# retr3d-testbench.net
KiCad netlist of a schematic drawn in EAGLE
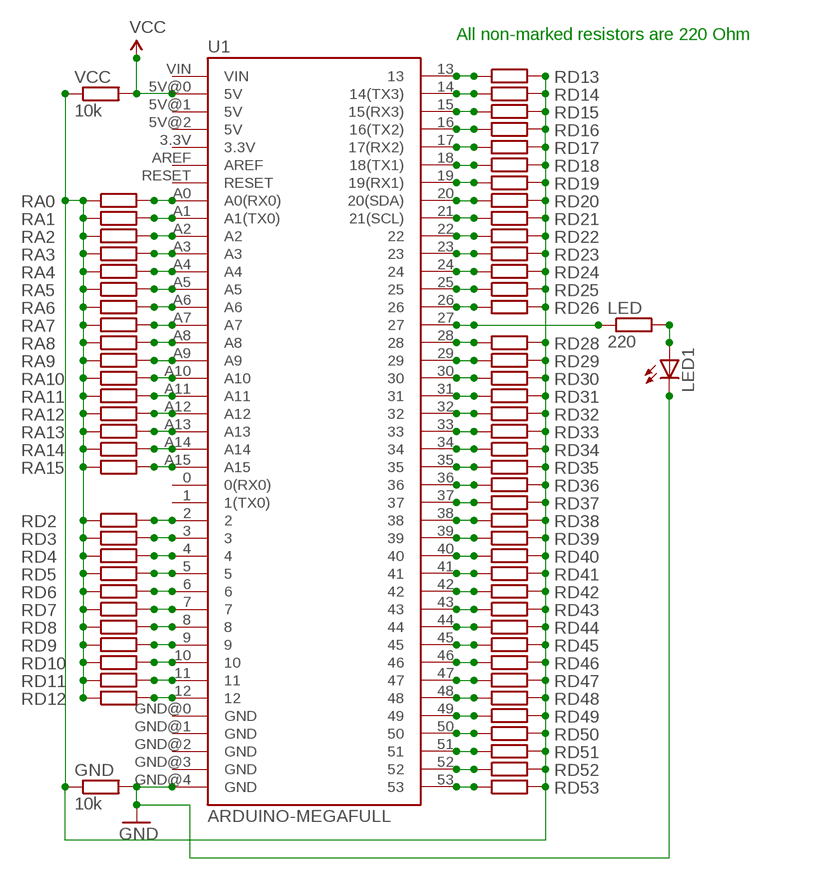
[diagram p0: schematic, sheet 1]

(export (version "E")
  (design (tool "Eeschema 10.0.6"))
  (components
    (comp (ref "GND")
      (value "10k")
      (footprint "eagle-import:0207_10")
      (libsource (lib "eagle-import") (part "R0207/10"))
    )
    (comp (ref "LED")
      (value "220")
      (footprint "eagle-import:0207_10")
      (libsource (lib "eagle-import") (part "R0207/10"))
    )
    (comp (ref "LED1")
      (value "LED5MM")
      (footprint "eagle-import:LED5MM")
      (libsource (lib "eagle-import") (part "LED5MM"))
    )
    (comp (ref "RA0")
      (value "220")
      (footprint "eagle-import:0207_10")
      (libsource (lib "eagle-import") (part "R0207/10"))
    )
    (comp (ref "RA1")
      (value "220")
      (footprint "eagle-import:0207_10")
      (libsource (lib "eagle-import") (part "R0207/10"))
    )
    (comp (ref "RA2")
      (value "220")
      (footprint "eagle-import:0207_10")
      (libsource (lib "eagle-import") (part "R0207/10"))
    )
    (comp (ref "RA3")
      (value "220")
      (footprint "eagle-import:0207_10")
      (libsource (lib "eagle-import") (part "R0207/10"))
    )
    (comp (ref "RA4")
      (value "220")
      (footprint "eagle-import:0207_10")
      (libsource (lib "eagle-import") (part "R0207/10"))
    )
    (comp (ref "RA5")
      (value "220")
      (footprint "eagle-import:0207_10")
      (libsource (lib "eagle-import") (part "R0207/10"))
    )
    (comp (ref "RA6")
      (value "220")
      (footprint "eagle-import:0207_10")
      (libsource (lib "eagle-import") (part "R0207/10"))
    )
    (comp (ref "RA7")
      (value "220")
      (footprint "eagle-import:0207_10")
      (libsource (lib "eagle-import") (part "R0207/10"))
    )
    (comp (ref "RA8")
      (value "220")
      (footprint "eagle-import:0207_10")
      (libsource (lib "eagle-import") (part "R0207/10"))
    )
    (comp (ref "RA9")
      (value "220")
      (footprint "eagle-import:0207_10")
      (libsource (lib "eagle-import") (part "R0207/10"))
    )
    (comp (ref "RA10")
      (value "220")
      (footprint "eagle-import:0207_10")
      (libsource (lib "eagle-import") (part "R0207/10"))
    )
    (comp (ref "RA11")
      (value "220")
      (footprint "eagle-import:0207_10")
      (libsource (lib "eagle-import") (part "R0207/10"))
    )
    (comp (ref "RA12")
      (value "220")
      (footprint "eagle-import:0207_10")
      (libsource (lib "eagle-import") (part "R0207/10"))
    )
    (comp (ref "RA13")
      (value "220")
      (footprint "eagle-import:0207_10")
      (libsource (lib "eagle-import") (part "R0207/10"))
    )
    (comp (ref "RA14")
      (value "220")
      (footprint "eagle-import:0207_10")
      (libsource (lib "eagle-import") (part "R0207/10"))
    )
    (comp (ref "RA15")
      (value "220")
      (footprint "eagle-import:0207_10")
      (libsource (lib "eagle-import") (part "R0207/10"))
    )
    (comp (ref "RD2")
      (value "220")
      (footprint "eagle-import:0207_10")
      (libsource (lib "eagle-import") (part "R0207/10"))
    )
    (comp (ref "RD3")
      (value "220")
      (footprint "eagle-import:0207_10")
      (libsource (lib "eagle-import") (part "R0207/10"))
    )
    (comp (ref "RD4")
      (value "220")
      (footprint "eagle-import:0207_10")
      (libsource (lib "eagle-import") (part "R0207/10"))
    )
    (comp (ref "RD5")
      (value "220")
      (footprint "eagle-import:0207_10")
      (libsource (lib "eagle-import") (part "R0207/10"))
    )
    (comp (ref "RD6")
      (value "220")
      (footprint "eagle-import:0207_10")
      (libsource (lib "eagle-import") (part "R0207/10"))
    )
    (comp (ref "RD7")
      (value "220")
      (footprint "eagle-import:0207_10")
      (libsource (lib "eagle-import") (part "R0207/10"))
    )
    (comp (ref "RD8")
      (value "220")
      (footprint "eagle-import:0207_10")
      (libsource (lib "eagle-import") (part "R0207/10"))
    )
    (comp (ref "RD9")
      (value "220")
      (footprint "eagle-import:0207_10")
      (libsource (lib "eagle-import") (part "R0207/10"))
    )
    (comp (ref "RD10")
      (value "220")
      (footprint "eagle-import:0207_10")
      (libsource (lib "eagle-import") (part "R0207/10"))
    )
    (comp (ref "RD11")
      (value "220")
      (footprint "eagle-import:0207_10")
      (libsource (lib "eagle-import") (part "R0207/10"))
    )
    (comp (ref "RD12")
      (value "220")
      (footprint "eagle-import:0207_10")
      (libsource (lib "eagle-import") (part "R0207/10"))
    )
    (comp (ref "RD13")
      (value "220")
      (footprint "eagle-import:0207_10")
      (libsource (lib "eagle-import") (part "R0207/10"))
    )
    (comp (ref "RD14")
      (value "220")
      (footprint "eagle-import:0207_10")
      (libsource (lib "eagle-import") (part "R0207/10"))
    )
    (comp (ref "RD15")
      (value "220")
      (footprint "eagle-import:0207_10")
      (libsource (lib "eagle-import") (part "R0207/10"))
    )
    (comp (ref "RD16")
      (value "220")
      (footprint "eagle-import:0207_10")
      (libsource (lib "eagle-import") (part "R0207/10"))
    )
    (comp (ref "RD17")
      (value "220")
      (footprint "eagle-import:0207_10")
      (libsource (lib "eagle-import") (part "R0207/10"))
    )
    (comp (ref "RD18")
      (value "220")
      (footprint "eagle-import:0207_10")
      (libsource (lib "eagle-import") (part "R0207/10"))
    )
    (comp (ref "RD19")
      (value "220")
      (footprint "eagle-import:0207_10")
      (libsource (lib "eagle-import") (part "R0207/10"))
    )
    (comp (ref "RD20")
      (value "220")
      (footprint "eagle-import:0207_10")
      (libsource (lib "eagle-import") (part "R0207/10"))
    )
    (comp (ref "RD21")
      (value "220")
      (footprint "eagle-import:0207_10")
      (libsource (lib "eagle-import") (part "R0207/10"))
    )
    (comp (ref "RD22")
      (value "220")
      (footprint "eagle-import:0207_10")
      (libsource (lib "eagle-import") (part "R0207/10"))
    )
    (comp (ref "RD23")
      (value "220")
      (footprint "eagle-import:0207_10")
      (libsource (lib "eagle-import") (part "R0207/10"))
    )
    (comp (ref "RD24")
      (value "220")
      (footprint "eagle-import:0207_10")
      (libsource (lib "eagle-import") (part "R0207/10"))
    )
    (comp (ref "RD25")
      (value "220")
      (footprint "eagle-import:0207_10")
      (libsource (lib "eagle-import") (part "R0207/10"))
    )
    (comp (ref "RD26")
      (value "220")
      (footprint "eagle-import:0207_10")
      (libsource (lib "eagle-import") (part "R0207/10"))
    )
    (comp (ref "RD28")
      (value "220")
      (footprint "eagle-import:0207_10")
      (libsource (lib "eagle-import") (part "R0207/10"))
    )
    (comp (ref "RD29")
      (value "220")
      (footprint "eagle-import:0207_10")
      (libsource (lib "eagle-import") (part "R0207/10"))
    )
    (comp (ref "RD30")
      (value "220")
      (footprint "eagle-import:0207_10")
      (libsource (lib "eagle-import") (part "R0207/10"))
    )
    (comp (ref "RD31")
      (value "220")
      (footprint "eagle-import:0207_10")
      (libsource (lib "eagle-import") (part "R0207/10"))
    )
    (comp (ref "RD32")
      (value "220")
      (footprint "eagle-import:0207_10")
      (libsource (lib "eagle-import") (part "R0207/10"))
    )
    (comp (ref "RD33")
      (value "220")
      (footprint "eagle-import:0207_10")
      (libsource (lib "eagle-import") (part "R0207/10"))
    )
    (comp (ref "RD34")
      (value "220")
      (footprint "eagle-import:0207_10")
      (libsource (lib "eagle-import") (part "R0207/10"))
    )
    (comp (ref "RD35")
      (value "220")
      (footprint "eagle-import:0207_10")
      (libsource (lib "eagle-import") (part "R0207/10"))
    )
    (comp (ref "RD36")
      (value "220")
      (footprint "eagle-import:0207_10")
      (libsource (lib "eagle-import") (part "R0207/10"))
    )
    (comp (ref "RD37")
      (value "220")
      (footprint "eagle-import:0207_10")
      (libsource (lib "eagle-import") (part "R0207/10"))
    )
    (comp (ref "RD38")
      (value "220")
      (footprint "eagle-import:0207_10")
      (libsource (lib "eagle-import") (part "R0207/10"))
    )
    (comp (ref "RD39")
      (value "220")
      (footprint "eagle-import:0207_10")
      (libsource (lib "eagle-import") (part "R0207/10"))
    )
    (comp (ref "RD40")
      (value "220")
      (footprint "eagle-import:0207_10")
      (libsource (lib "eagle-import") (part "R0207/10"))
    )
    (comp (ref "RD41")
      (value "220")
      (footprint "eagle-import:0207_10")
      (libsource (lib "eagle-import") (part "R0207/10"))
    )
    (comp (ref "RD42")
      (value "220")
      (footprint "eagle-import:0207_10")
      (libsource (lib "eagle-import") (part "R0207/10"))
    )
    (comp (ref "RD43")
      (value "220")
      (footprint "eagle-import:0207_10")
      (libsource (lib "eagle-import") (part "R0207/10"))
    )
    (comp (ref "RD44")
      (value "220")
      (footprint "eagle-import:0207_10")
      (libsource (lib "eagle-import") (part "R0207/10"))
    )
    (comp (ref "RD45")
      (value "220")
      (footprint "eagle-import:0207_10")
      (libsource (lib "eagle-import") (part "R0207/10"))
    )
    (comp (ref "RD46")
      (value "220")
      (footprint "eagle-import:0207_10")
      (libsource (lib "eagle-import") (part "R0207/10"))
    )
    (comp (ref "RD47")
      (value "220")
      (footprint "eagle-import:0207_10")
      (libsource (lib "eagle-import") (part "R0207/10"))
    )
    (comp (ref "RD48")
      (value "220")
      (footprint "eagle-import:0207_10")
      (libsource (lib "eagle-import") (part "R0207/10"))
    )
    (comp (ref "RD49")
      (value "220")
      (footprint "eagle-import:0207_10")
      (libsource (lib "eagle-import") (part "R0207/10"))
    )
    (comp (ref "RD50")
      (value "220")
      (footprint "eagle-import:0207_10")
      (libsource (lib "eagle-import") (part "R0207/10"))
    )
    (comp (ref "RD51")
      (value "220")
      (footprint "eagle-import:0207_10")
      (libsource (lib "eagle-import") (part "R0207/10"))
    )
    (comp (ref "RD52")
      (value "220")
      (footprint "eagle-import:0207_10")
      (libsource (lib "eagle-import") (part "R0207/10"))
    )
    (comp (ref "RD53")
      (value "220")
      (footprint "eagle-import:0207_10")
      (libsource (lib "eagle-import") (part "R0207/10"))
    )
    (comp (ref "U1")
      (value "ARDUINO-MEGAFULL")
      (footprint "eagle-import:ARDUINO_MEGA")
      (libsource (lib "eagle-import") (part "ARDUINO-MEGAFULL"))
    )
    (comp (ref "VCC")
      (value "10k")
      (footprint "eagle-import:0207_10")
      (libsource (lib "eagle-import") (part "R0207/10"))
    )
  )
  (nets
    (net (code "1") (name "GND") (class "Default")
      (node (ref "GND") (pin "2") (pinfunction "2_2") (pintype "passive"))
      (node (ref "LED1") (pin "K") (pinfunction "C_K") (pintype "passive"))
      (node (ref "U1") (pin "GND@4") (pinfunction "GND_GND@4") (pintype "bidirectional"))
    )
    (net (code "2") (name "Net-(GND-Pad1)") (class "Default")
      (node (ref "GND") (pin "1") (pinfunction "1_1") (pintype "passive"))
      (node (ref "RA0") (pin "1") (pinfunction "1_1") (pintype "passive"))
      (node (ref "RA1") (pin "1") (pinfunction "1_1") (pintype "passive"))
      (node (ref "RA10") (pin "1") (pinfunction "1_1") (pintype "passive"))
      (node (ref "RA11") (pin "1") (pinfunction "1_1") (pintype "passive"))
      (node (ref "RA12") (pin "1") (pinfunction "1_1") (pintype "passive"))
      (node (ref "RA13") (pin "1") (pinfunction "1_1") (pintype "passive"))
      (node (ref "RA14") (pin "1") (pinfunction "1_1") (pintype "passive"))
      (node (ref "RA15") (pin "1") (pinfunction "1_1") (pintype "passive"))
      (node (ref "RA2") (pin "1") (pinfunction "1_1") (pintype "passive"))
      (node (ref "RA3") (pin "1") (pinfunction "1_1") (pintype "passive"))
      (node (ref "RA4") (pin "1") (pinfunction "1_1") (pintype "passive"))
      (node (ref "RA5") (pin "1") (pinfunction "1_1") (pintype "passive"))
      (node (ref "RA6") (pin "1") (pinfunction "1_1") (pintype "passive"))
      (node (ref "RA7") (pin "1") (pinfunction "1_1") (pintype "passive"))
      (node (ref "RA8") (pin "1") (pinfunction "1_1") (pintype "passive"))
      (node (ref "RA9") (pin "1") (pinfunction "1_1") (pintype "passive"))
      (node (ref "RD10") (pin "1") (pinfunction "1_1") (pintype "passive"))
      (node (ref "RD11") (pin "1") (pinfunction "1_1") (pintype "passive"))
      (node (ref "RD12") (pin "1") (pinfunction "1_1") (pintype "passive"))
      (node (ref "RD13") (pin "2") (pinfunction "2_2") (pintype "passive"))
      (node (ref "RD14") (pin "2") (pinfunction "2_2") (pintype "passive"))
      (node (ref "RD15") (pin "2") (pinfunction "2_2") (pintype "passive"))
      (node (ref "RD16") (pin "2") (pinfunction "2_2") (pintype "passive"))
      (node (ref "RD17") (pin "2") (pinfunction "2_2") (pintype "passive"))
      (node (ref "RD18") (pin "2") (pinfunction "2_2") (pintype "passive"))
      (node (ref "RD19") (pin "2") (pinfunction "2_2") (pintype "passive"))
      (node (ref "RD2") (pin "1") (pinfunction "1_1") (pintype "passive"))
      (node (ref "RD20") (pin "2") (pinfunction "2_2") (pintype "passive"))
      (node (ref "RD21") (pin "2") (pinfunction "2_2") (pintype "passive"))
      (node (ref "RD22") (pin "2") (pinfunction "2_2") (pintype "passive"))
      (node (ref "RD23") (pin "2") (pinfunction "2_2") (pintype "passive"))
      (node (ref "RD24") (pin "2") (pinfunction "2_2") (pintype "passive"))
      (node (ref "RD25") (pin "2") (pinfunction "2_2") (pintype "passive"))
      (node (ref "RD26") (pin "2") (pinfunction "2_2") (pintype "passive"))
      (node (ref "RD28") (pin "2") (pinfunction "2_2") (pintype "passive"))
      (node (ref "RD29") (pin "2") (pinfunction "2_2") (pintype "passive"))
      (node (ref "RD3") (pin "1") (pinfunction "1_1") (pintype "passive"))
      (node (ref "RD30") (pin "2") (pinfunction "2_2") (pintype "passive"))
      (node (ref "RD31") (pin "2") (pinfunction "2_2") (pintype "passive"))
      (node (ref "RD32") (pin "2") (pinfunction "2_2") (pintype "passive"))
      (node (ref "RD33") (pin "2") (pinfunction "2_2") (pintype "passive"))
      (node (ref "RD34") (pin "2") (pinfunction "2_2") (pintype "passive"))
      (node (ref "RD35") (pin "2") (pinfunction "2_2") (pintype "passive"))
      (node (ref "RD36") (pin "2") (pinfunction "2_2") (pintype "passive"))
      (node (ref "RD37") (pin "2") (pinfunction "2_2") (pintype "passive"))
      (node (ref "RD38") (pin "2") (pinfunction "2_2") (pintype "passive"))
      (node (ref "RD39") (pin "2") (pinfunction "2_2") (pintype "passive"))
      (node (ref "RD4") (pin "1") (pinfunction "1_1") (pintype "passive"))
      (node (ref "RD40") (pin "2") (pinfunction "2_2") (pintype "passive"))
      (node (ref "RD41") (pin "2") (pinfunction "2_2") (pintype "passive"))
      (node (ref "RD42") (pin "2") (pinfunction "2_2") (pintype "passive"))
      (node (ref "RD43") (pin "2") (pinfunction "2_2") (pintype "passive"))
      (node (ref "RD44") (pin "2") (pinfunction "2_2") (pintype "passive"))
      (node (ref "RD45") (pin "2") (pinfunction "2_2") (pintype "passive"))
      (node (ref "RD46") (pin "2") (pinfunction "2_2") (pintype "passive"))
      (node (ref "RD47") (pin "2") (pinfunction "2_2") (pintype "passive"))
      (node (ref "RD48") (pin "2") (pinfunction "2_2") (pintype "passive"))
      (node (ref "RD49") (pin "2") (pinfunction "2_2") (pintype "passive"))
      (node (ref "RD5") (pin "1") (pinfunction "1_1") (pintype "passive"))
      (node (ref "RD50") (pin "2") (pinfunction "2_2") (pintype "passive"))
      (node (ref "RD51") (pin "2") (pinfunction "2_2") (pintype "passive"))
      (node (ref "RD52") (pin "2") (pinfunction "2_2") (pintype "passive"))
      (node (ref "RD53") (pin "2") (pinfunction "2_2") (pintype "passive"))
      (node (ref "RD6") (pin "1") (pinfunction "1_1") (pintype "passive"))
      (node (ref "RD7") (pin "1") (pinfunction "1_1") (pintype "passive"))
      (node (ref "RD8") (pin "1") (pinfunction "1_1") (pintype "passive"))
      (node (ref "RD9") (pin "1") (pinfunction "1_1") (pintype "passive"))
      (node (ref "VCC") (pin "1") (pinfunction "1_1") (pintype "passive"))
    )
    (net (code "3") (name "Net-(LED-Pad1)") (class "Default")
      (node (ref "LED") (pin "1") (pinfunction "1_1") (pintype "passive"))
      (node (ref "U1") (pin "27") (pinfunction "27_27") (pintype "bidirectional"))
    )
    (net (code "4") (name "Net-(LED-Pad2)") (class "Default")
      (node (ref "LED") (pin "2") (pinfunction "2_2") (pintype "passive"))
      (node (ref "LED1") (pin "A") (pinfunction "A_A") (pintype "passive"))
    )
    (net (code "5") (name "Net-(RA2-Pad2)") (class "Default")
      (node (ref "RA2") (pin "2") (pinfunction "2_2") (pintype "passive"))
      (node (ref "U1") (pin "A2") (pinfunction "A2_A2") (pintype "bidirectional"))
    )
    (net (code "6") (name "Net-(RA3-Pad2)") (class "Default")
      (node (ref "RA3") (pin "2") (pinfunction "2_2") (pintype "passive"))
      (node (ref "U1") (pin "A3") (pinfunction "A3_A3") (pintype "bidirectional"))
    )
    (net (code "7") (name "Net-(RA4-Pad2)") (class "Default")
      (node (ref "RA4") (pin "2") (pinfunction "2_2") (pintype "passive"))
      (node (ref "U1") (pin "A4") (pinfunction "A4_A4") (pintype "bidirectional"))
    )
    (net (code "8") (name "Net-(RA5-Pad2)") (class "Default")
      (node (ref "RA5") (pin "2") (pinfunction "2_2") (pintype "passive"))
      (node (ref "U1") (pin "A5") (pinfunction "A5_A5") (pintype "bidirectional"))
    )
    (net (code "9") (name "Net-(RA6-Pad2)") (class "Default")
      (node (ref "RA6") (pin "2") (pinfunction "2_2") (pintype "passive"))
      (node (ref "U1") (pin "A6") (pinfunction "A6_A6") (pintype "bidirectional"))
    )
    (net (code "10") (name "Net-(RA7-Pad2)") (class "Default")
      (node (ref "RA7") (pin "2") (pinfunction "2_2") (pintype "passive"))
      (node (ref "U1") (pin "A7") (pinfunction "A7_A7") (pintype "bidirectional"))
    )
    (net (code "11") (name "Net-(RA8-Pad2)") (class "Default")
      (node (ref "RA8") (pin "2") (pinfunction "2_2") (pintype "passive"))
      (node (ref "U1") (pin "A8") (pinfunction "A8_A8") (pintype "bidirectional"))
    )
    (net (code "12") (name "Net-(RA9-Pad2)") (class "Default")
      (node (ref "RA9") (pin "2") (pinfunction "2_2") (pintype "passive"))
      (node (ref "U1") (pin "A9") (pinfunction "A9_A9") (pintype "bidirectional"))
    )
    (net (code "13") (name "Net-(RA10-Pad2)") (class "Default")
      (node (ref "RA10") (pin "2") (pinfunction "2_2") (pintype "passive"))
      (node (ref "U1") (pin "A10") (pinfunction "A10_A10") (pintype "bidirectional"))
    )
    (net (code "14") (name "Net-(RA11-Pad2)") (class "Default")
      (node (ref "RA11") (pin "2") (pinfunction "2_2") (pintype "passive"))
      (node (ref "U1") (pin "A11") (pinfunction "A11_A11") (pintype "bidirectional"))
    )
    (net (code "15") (name "Net-(RA12-Pad2)") (class "Default")
      (node (ref "RA12") (pin "2") (pinfunction "2_2") (pintype "passive"))
      (node (ref "U1") (pin "A12") (pinfunction "A12_A12") (pintype "bidirectional"))
    )
    (net (code "16") (name "Net-(RA13-Pad2)") (class "Default")
      (node (ref "RA13") (pin "2") (pinfunction "2_2") (pintype "passive"))
      (node (ref "U1") (pin "A13") (pinfunction "A13_A13") (pintype "bidirectional"))
    )
    (net (code "17") (name "Net-(RA14-Pad2)") (class "Default")
      (node (ref "RA14") (pin "2") (pinfunction "2_2") (pintype "passive"))
      (node (ref "U1") (pin "A14") (pinfunction "A14_A14") (pintype "bidirectional"))
    )
    (net (code "18") (name "Net-(RA15-Pad2)") (class "Default")
      (node (ref "RA15") (pin "2") (pinfunction "2_2") (pintype "passive"))
      (node (ref "U1") (pin "A15") (pinfunction "A15_A15") (pintype "bidirectional"))
    )
    (net (code "19") (name "Net-(RD2-Pad2)") (class "Default")
      (node (ref "RD2") (pin "2") (pinfunction "2_2") (pintype "passive"))
      (node (ref "U1") (pin "2") (pinfunction "2_2") (pintype "bidirectional"))
    )
    (net (code "20") (name "Net-(RD3-Pad2)") (class "Default")
      (node (ref "RD3") (pin "2") (pinfunction "2_2") (pintype "passive"))
      (node (ref "U1") (pin "3") (pinfunction "3_3") (pintype "bidirectional"))
    )
    (net (code "21") (name "Net-(RD4-Pad2)") (class "Default")
      (node (ref "RD4") (pin "2") (pinfunction "2_2") (pintype "passive"))
      (node (ref "U1") (pin "4") (pinfunction "4_4") (pintype "bidirectional"))
    )
    (net (code "22") (name "Net-(RD5-Pad2)") (class "Default")
      (node (ref "RD5") (pin "2") (pinfunction "2_2") (pintype "passive"))
      (node (ref "U1") (pin "5") (pinfunction "5_5") (pintype "bidirectional"))
    )
    (net (code "23") (name "Net-(RD6-Pad2)") (class "Default")
      (node (ref "RD6") (pin "2") (pinfunction "2_2") (pintype "passive"))
      (node (ref "U1") (pin "6") (pinfunction "6_6") (pintype "bidirectional"))
    )
    (net (code "24") (name "Net-(RD7-Pad2)") (class "Default")
      (node (ref "RD7") (pin "2") (pinfunction "2_2") (pintype "passive"))
      (node (ref "U1") (pin "7") (pinfunction "7_7") (pintype "bidirectional"))
    )
    (net (code "25") (name "Net-(RD8-Pad2)") (class "Default")
      (node (ref "RD8") (pin "2") (pinfunction "2_2") (pintype "passive"))
      (node (ref "U1") (pin "8") (pinfunction "8_8") (pintype "bidirectional"))
    )
    (net (code "26") (name "Net-(RD9-Pad2)") (class "Default")
      (node (ref "RD9") (pin "2") (pinfunction "2_2") (pintype "passive"))
      (node (ref "U1") (pin "9") (pinfunction "9_9") (pintype "bidirectional"))
    )
    (net (code "27") (name "Net-(RD10-Pad2)") (class "Default")
      (node (ref "RD10") (pin "2") (pinfunction "2_2") (pintype "passive"))
      (node (ref "U1") (pin "10") (pinfunction "10_10") (pintype "bidirectional"))
    )
    (net (code "28") (name "Net-(RD11-Pad2)") (class "Default")
      (node (ref "RD11") (pin "2") (pinfunction "2_2") (pintype "passive"))
      (node (ref "U1") (pin "11") (pinfunction "11_11") (pintype "bidirectional"))
    )
    (net (code "29") (name "Net-(RD12-Pad2)") (class "Default")
      (node (ref "RD12") (pin "2") (pinfunction "2_2") (pintype "passive"))
      (node (ref "U1") (pin "12") (pinfunction "12_12") (pintype "bidirectional"))
    )
    (net (code "30") (name "Net-(RD13-Pad1)") (class "Default")
      (node (ref "RD13") (pin "1") (pinfunction "1_1") (pintype "passive"))
      (node (ref "U1") (pin "13") (pinfunction "13_13") (pintype "bidirectional"))
    )
    (net (code "31") (name "Net-(RD22-Pad1)") (class "Default")
      (node (ref "RD22") (pin "1") (pinfunction "1_1") (pintype "passive"))
      (node (ref "U1") (pin "22") (pinfunction "22_22") (pintype "bidirectional"))
    )
    (net (code "32") (name "Net-(RD23-Pad1)") (class "Default")
      (node (ref "RD23") (pin "1") (pinfunction "1_1") (pintype "passive"))
      (node (ref "U1") (pin "23") (pinfunction "23_23") (pintype "bidirectional"))
    )
    (net (code "33") (name "Net-(RD24-Pad1)") (class "Default")
      (node (ref "RD24") (pin "1") (pinfunction "1_1") (pintype "passive"))
      (node (ref "U1") (pin "24") (pinfunction "24_24") (pintype "bidirectional"))
    )
    (net (code "34") (name "Net-(RD25-Pad1)") (class "Default")
      (node (ref "RD25") (pin "1") (pinfunction "1_1") (pintype "passive"))
      (node (ref "U1") (pin "25") (pinfunction "25_25") (pintype "bidirectional"))
    )
    (net (code "35") (name "Net-(RD26-Pad1)") (class "Default")
      (node (ref "RD26") (pin "1") (pinfunction "1_1") (pintype "passive"))
      (node (ref "U1") (pin "26") (pinfunction "26_26") (pintype "bidirectional"))
    )
    (net (code "36") (name "Net-(RD28-Pad1)") (class "Default")
      (node (ref "RD28") (pin "1") (pinfunction "1_1") (pintype "passive"))
      (node (ref "U1") (pin "28") (pinfunction "28_28") (pintype "bidirectional"))
    )
    (net (code "37") (name "Net-(RD29-Pad1)") (class "Default")
      (node (ref "RD29") (pin "1") (pinfunction "1_1") (pintype "passive"))
      (node (ref "U1") (pin "29") (pinfunction "29_29") (pintype "bidirectional"))
    )
    (net (code "38") (name "Net-(RD30-Pad1)") (class "Default")
      (node (ref "RD30") (pin "1") (pinfunction "1_1") (pintype "passive"))
      (node (ref "U1") (pin "30") (pinfunction "30_30") (pintype "bidirectional"))
    )
    (net (code "39") (name "Net-(RD31-Pad1)") (class "Default")
      (node (ref "RD31") (pin "1") (pinfunction "1_1") (pintype "passive"))
      (node (ref "U1") (pin "31") (pinfunction "31_31") (pintype "bidirectional"))
    )
    (net (code "40") (name "Net-(RD32-Pad1)") (class "Default")
      (node (ref "RD32") (pin "1") (pinfunction "1_1") (pintype "passive"))
      (node (ref "U1") (pin "32") (pinfunction "32_32") (pintype "bidirectional"))
    )
    (net (code "41") (name "Net-(RD33-Pad1)") (class "Default")
      (node (ref "RD33") (pin "1") (pinfunction "1_1") (pintype "passive"))
      (node (ref "U1") (pin "33") (pinfunction "33_33") (pintype "bidirectional"))
    )
    (net (code "42") (name "Net-(RD34-Pad1)") (class "Default")
      (node (ref "RD34") (pin "1") (pinfunction "1_1") (pintype "passive"))
      (node (ref "U1") (pin "34") (pinfunction "34_34") (pintype "bidirectional"))
    )
    (net (code "43") (name "Net-(RD35-Pad1)") (class "Default")
      (node (ref "RD35") (pin "1") (pinfunction "1_1") (pintype "passive"))
      (node (ref "U1") (pin "35") (pinfunction "35_35") (pintype "bidirectional"))
    )
    (net (code "44") (name "Net-(RD36-Pad1)") (class "Default")
      (node (ref "RD36") (pin "1") (pinfunction "1_1") (pintype "passive"))
      (node (ref "U1") (pin "36") (pinfunction "36_36") (pintype "bidirectional"))
    )
    (net (code "45") (name "Net-(RD37-Pad1)") (class "Default")
      (node (ref "RD37") (pin "1") (pinfunction "1_1") (pintype "passive"))
      (node (ref "U1") (pin "37") (pinfunction "37_37") (pintype "bidirectional"))
    )
    (net (code "46") (name "Net-(RD38-Pad1)") (class "Default")
      (node (ref "RD38") (pin "1") (pinfunction "1_1") (pintype "passive"))
      (node (ref "U1") (pin "38") (pinfunction "38_38") (pintype "bidirectional"))
    )
    (net (code "47") (name "Net-(RD39-Pad1)") (class "Default")
      (node (ref "RD39") (pin "1") (pinfunction "1_1") (pintype "passive"))
      (node (ref "U1") (pin "39") (pinfunction "39_39") (pintype "bidirectional"))
    )
    (net (code "48") (name "Net-(RD40-Pad1)") (class "Default")
      (node (ref "RD40") (pin "1") (pinfunction "1_1") (pintype "passive"))
      (node (ref "U1") (pin "40") (pinfunction "40_40") (pintype "bidirectional"))
    )
    (net (code "49") (name "Net-(RD41-Pad1)") (class "Default")
      (node (ref "RD41") (pin "1") (pinfunction "1_1") (pintype "passive"))
      (node (ref "U1") (pin "41") (pinfunction "41_41") (pintype "bidirectional"))
    )
    (net (code "50") (name "Net-(RD42-Pad1)") (class "Default")
      (node (ref "RD42") (pin "1") (pinfunction "1_1") (pintype "passive"))
      (node (ref "U1") (pin "42") (pinfunction "42_42") (pintype "bidirectional"))
    )
    (net (code "51") (name "Net-(RD43-Pad1)") (class "Default")
      (node (ref "RD43") (pin "1") (pinfunction "1_1") (pintype "passive"))
      (node (ref "U1") (pin "43") (pinfunction "43_43") (pintype "bidirectional"))
    )
    (net (code "52") (name "Net-(RD44-Pad1)") (class "Default")
      (node (ref "RD44") (pin "1") (pinfunction "1_1") (pintype "passive"))
      (node (ref "U1") (pin "44") (pinfunction "44_44") (pintype "bidirectional"))
    )
    (net (code "53") (name "Net-(RD45-Pad1)") (class "Default")
      (node (ref "RD45") (pin "1") (pinfunction "1_1") (pintype "passive"))
      (node (ref "U1") (pin "45") (pinfunction "45_45") (pintype "bidirectional"))
    )
    (net (code "54") (name "Net-(RD46-Pad1)") (class "Default")
      (node (ref "RD46") (pin "1") (pinfunction "1_1") (pintype "passive"))
      (node (ref "U1") (pin "46") (pinfunction "46_46") (pintype "bidirectional"))
    )
    (net (code "55") (name "Net-(RD47-Pad1)") (class "Default")
      (node (ref "RD47") (pin "1") (pinfunction "1_1") (pintype "passive"))
      (node (ref "U1") (pin "47") (pinfunction "47_47") (pintype "bidirectional"))
    )
    (net (code "56") (name "Net-(RD48-Pad1)") (class "Default")
      (node (ref "RD48") (pin "1") (pinfunction "1_1") (pintype "passive"))
      (node (ref "U1") (pin "48") (pinfunction "48_48") (pintype "bidirectional"))
    )
    (net (code "57") (name "Net-(RD49-Pad1)") (class "Default")
      (node (ref "RD49") (pin "1") (pinfunction "1_1") (pintype "passive"))
      (node (ref "U1") (pin "49") (pinfunction "49_49") (pintype "bidirectional"))
    )
    (net (code "58") (name "Net-(RD50-Pad1)") (class "Default")
      (node (ref "RD50") (pin "1") (pinfunction "1_1") (pintype "passive"))
      (node (ref "U1") (pin "50") (pinfunction "50_50") (pintype "bidirectional"))
    )
    (net (code "59") (name "Net-(RD51-Pad1)") (class "Default")
      (node (ref "RD51") (pin "1") (pinfunction "1_1") (pintype "passive"))
      (node (ref "U1") (pin "51") (pinfunction "51_51") (pintype "bidirectional"))
    )
    (net (code "60") (name "Net-(RD52-Pad1)") (class "Default")
      (node (ref "RD52") (pin "1") (pinfunction "1_1") (pintype "passive"))
      (node (ref "U1") (pin "52") (pinfunction "52_52") (pintype "bidirectional"))
    )
    (net (code "61") (name "Net-(RD53-Pad1)") (class "Default")
      (node (ref "RD53") (pin "1") (pinfunction "1_1") (pintype "passive"))
      (node (ref "U1") (pin "53") (pinfunction "53_53") (pintype "bidirectional"))
    )
    (net (code "62") (name "Net-(U1-14(TX3))") (class "Default")
      (node (ref "RD14") (pin "1") (pinfunction "1_1") (pintype "passive"))
      (node (ref "U1") (pin "14") (pinfunction "14(TX3)_14") (pintype "bidirectional"))
    )
    (net (code "63") (name "Net-(U1-15(RX3))") (class "Default")
      (node (ref "RD15") (pin "1") (pinfunction "1_1") (pintype "passive"))
      (node (ref "U1") (pin "15") (pinfunction "15(RX3)_15") (pintype "bidirectional"))
    )
    (net (code "64") (name "Net-(U1-16(TX2))") (class "Default")
      (node (ref "RD16") (pin "1") (pinfunction "1_1") (pintype "passive"))
      (node (ref "U1") (pin "16") (pinfunction "16(TX2)_16") (pintype "bidirectional"))
    )
    (net (code "65") (name "Net-(U1-17(RX2))") (class "Default")
      (node (ref "RD17") (pin "1") (pinfunction "1_1") (pintype "passive"))
      (node (ref "U1") (pin "17") (pinfunction "17(RX2)_17") (pintype "bidirectional"))
    )
    (net (code "66") (name "Net-(U1-18(TX1))") (class "Default")
      (node (ref "RD18") (pin "1") (pinfunction "1_1") (pintype "passive"))
      (node (ref "U1") (pin "18") (pinfunction "18(TX1)_18") (pintype "bidirectional"))
    )
    (net (code "67") (name "Net-(U1-19(RX1))") (class "Default")
      (node (ref "RD19") (pin "1") (pinfunction "1_1") (pintype "passive"))
      (node (ref "U1") (pin "19") (pinfunction "19(RX1)_19") (pintype "bidirectional"))
    )
    (net (code "68") (name "Net-(U1-20(SDA))") (class "Default")
      (node (ref "RD20") (pin "1") (pinfunction "1_1") (pintype "passive"))
      (node (ref "U1") (pin "20") (pinfunction "20(SDA)_20") (pintype "bidirectional"))
    )
    (net (code "69") (name "Net-(U1-21(SCL))") (class "Default")
      (node (ref "RD21") (pin "1") (pinfunction "1_1") (pintype "passive"))
      (node (ref "U1") (pin "21") (pinfunction "21(SCL)_21") (pintype "bidirectional"))
    )
    (net (code "70") (name "Net-(U1-A0(RX0))") (class "Default")
      (node (ref "RA0") (pin "2") (pinfunction "2_2") (pintype "passive"))
      (node (ref "U1") (pin "A0") (pinfunction "A0(RX0)_A0") (pintype "bidirectional"))
    )
    (net (code "71") (name "Net-(U1-A1(TX0))") (class "Default")
      (node (ref "RA1") (pin "2") (pinfunction "2_2") (pintype "passive"))
      (node (ref "U1") (pin "A1") (pinfunction "A1(TX0)_A1") (pintype "bidirectional"))
    )
    (net (code "72") (name "VCC") (class "Default")
      (node (ref "U1") (pin "5V@0") (pinfunction "5V_5V@0") (pintype "bidirectional"))
      (node (ref "VCC") (pin "2") (pinfunction "2_2") (pintype "passive"))
    )
    (net (code "73") (name "unconnected-(U1-0(RX0)-Pad0)") (class "Default")
      (node (ref "U1") (pin "0") (pinfunction "0(RX0)_0") (pintype "bidirectional"))
    )
    (net (code "74") (name "unconnected-(U1-1(TX0)-Pad1)") (class "Default")
      (node (ref "U1") (pin "1") (pinfunction "1(TX0)_1") (pintype "bidirectional"))
    )
    (net (code "75") (name "unconnected-(U1-5V-Pad5V@1)") (class "Default")
      (node (ref "U1") (pin "5V@1") (pinfunction "5V_5V@1") (pintype "bidirectional"))
    )
    (net (code "76") (name "unconnected-(U1-5V-Pad5V@2)") (class "Default")
      (node (ref "U1") (pin "5V@2") (pinfunction "5V_5V@2") (pintype "bidirectional"))
    )
    (net (code "77") (name "unconnected-(U1-GND-PadGND@0)") (class "Default")
      (node (ref "U1") (pin "GND@0") (pinfunction "GND_GND@0") (pintype "bidirectional"))
    )
    (net (code "78") (name "unconnected-(U1-GND-PadGND@1)") (class "Default")
      (node (ref "U1") (pin "GND@1") (pinfunction "GND_GND@1") (pintype "bidirectional"))
    )
    (net (code "79") (name "unconnected-(U1-GND-PadGND@2)") (class "Default")
      (node (ref "U1") (pin "GND@2") (pinfunction "GND_GND@2") (pintype "bidirectional"))
    )
    (net (code "80") (name "unconnected-(U1-GND-PadGND@3)") (class "Default")
      (node (ref "U1") (pin "GND@3") (pinfunction "GND_GND@3") (pintype "bidirectional"))
    )
    (net (code "81") (name "unconnected-(U1-Pad3.3V)") (class "Default")
      (node (ref "U1") (pin "3.3V") (pinfunction "3.3V_3.3V") (pintype "bidirectional"))
    )
    (net (code "82") (name "unconnected-(U1-PadAREF)") (class "Default")
      (node (ref "U1") (pin "AREF") (pinfunction "AREF_AREF") (pintype "bidirectional"))
    )
    (net (code "83") (name "unconnected-(U1-PadRESET)") (class "Default")
      (node (ref "U1") (pin "RESET") (pinfunction "RESET_RESET") (pintype "bidirectional"))
    )
    (net (code "84") (name "unconnected-(U1-PadVIN)") (class "Default")
      (node (ref "U1") (pin "VIN") (pinfunction "VIN_VIN") (pintype "bidirectional"))
    )
  )
)
